# Schematic.net
KiCad netlist of a schematic drawn in EAGLE
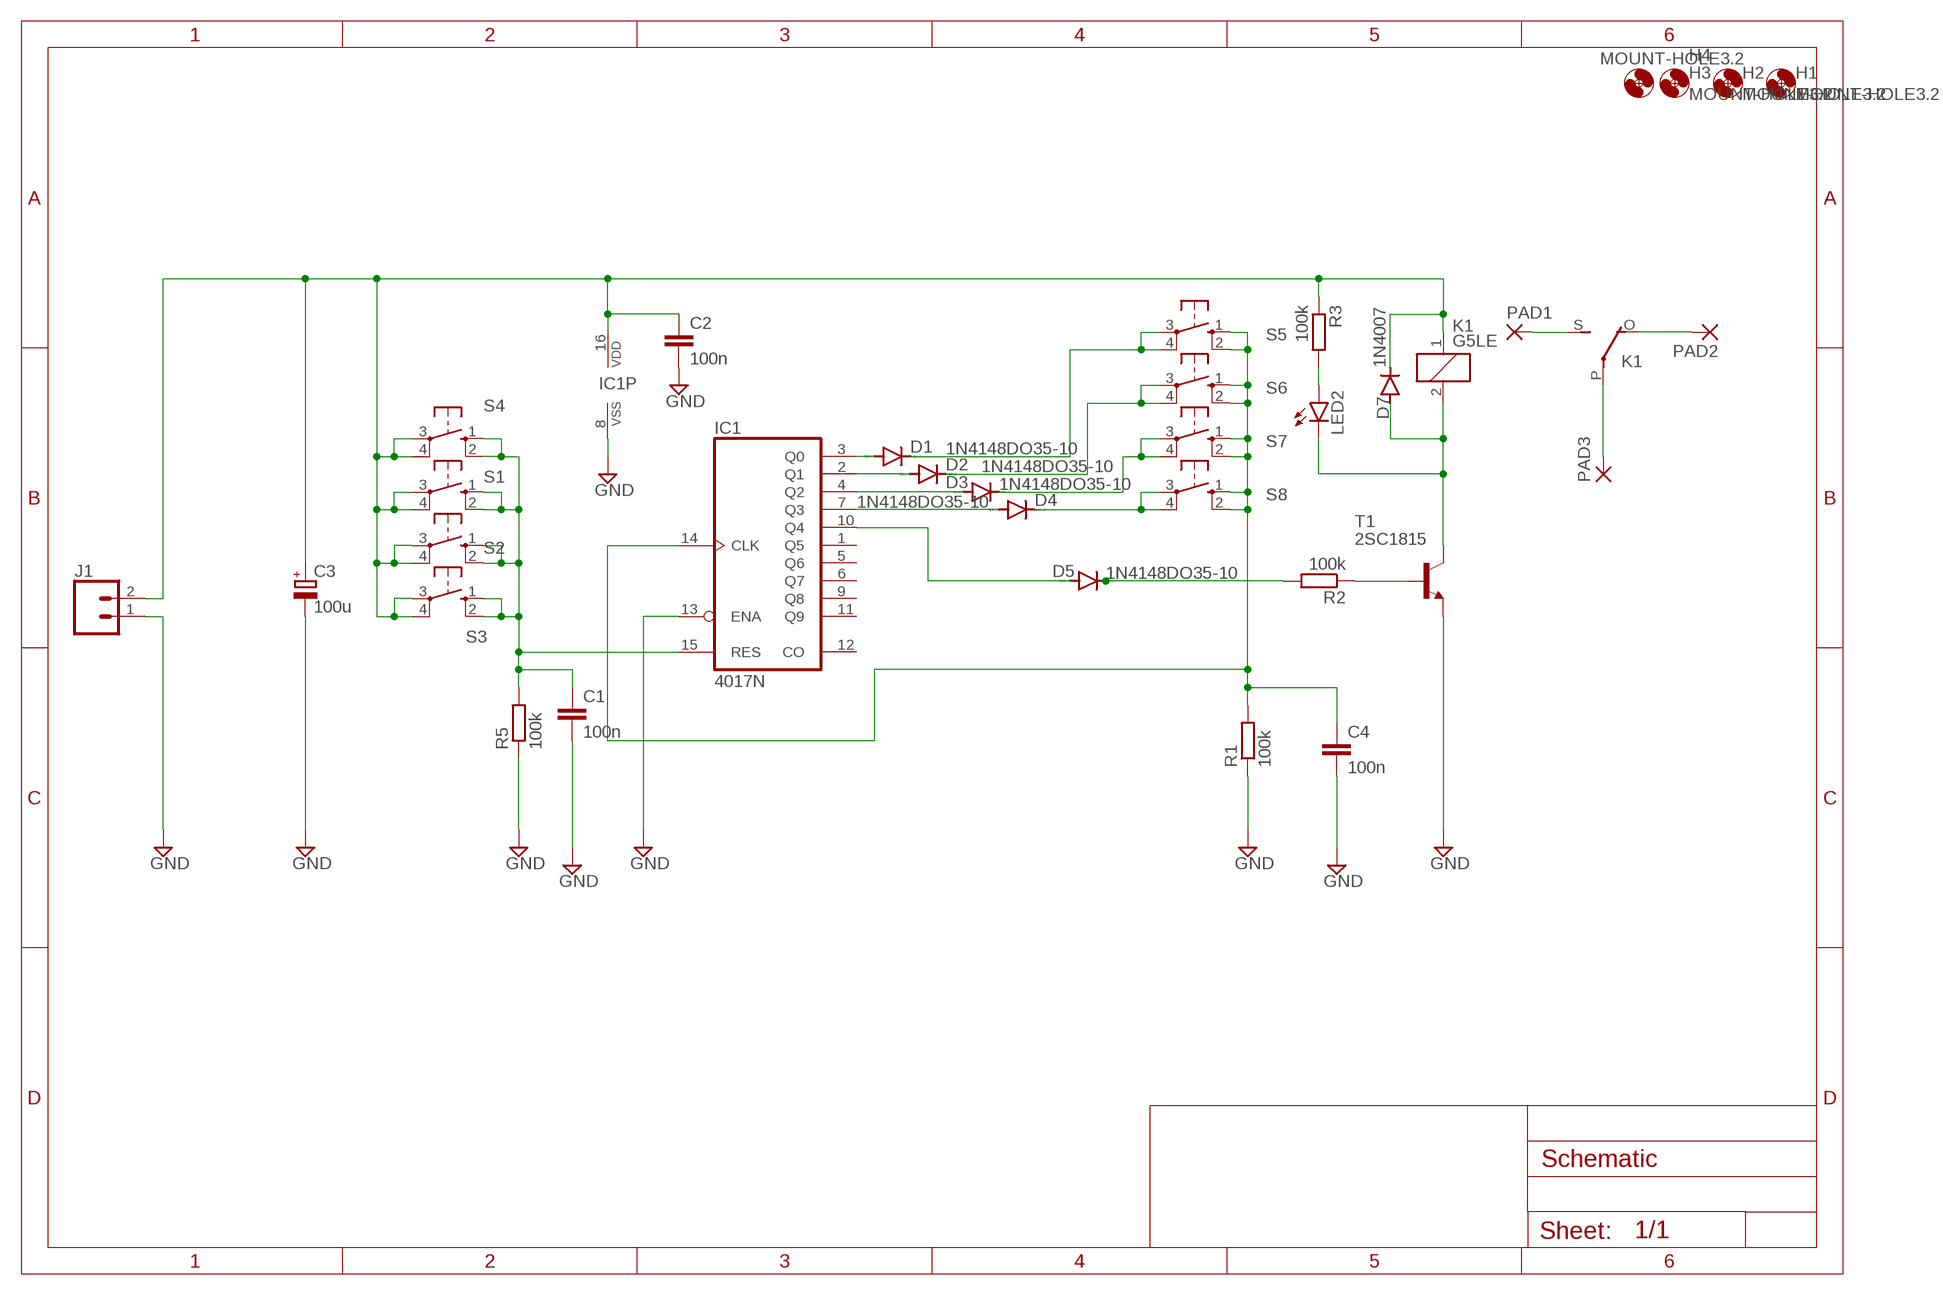
[diagram p0: schematic, sheet 1]

(export (version "E")
  (design (tool "Eeschema 10.0.6"))
  (components
    (comp (ref "C1")
      (value "100n")
      (footprint "eagle-import:C025-060X050")
      (libsource (lib "eagle-import") (part "C-EU025-060X050"))
    )
    (comp (ref "C2")
      (value "100n")
      (footprint "eagle-import:C025-060X050")
      (libsource (lib "eagle-import") (part "C-EU025-060X050"))
    )
    (comp (ref "C3")
      (value "100u")
      (footprint "eagle-import:E2,5-6")
      (libsource (lib "eagle-import") (part "CPOL-EUE2.5-6"))
    )
    (comp (ref "C4")
      (value "100n")
      (footprint "eagle-import:C025-060X050")
      (libsource (lib "eagle-import") (part "C-EU025-060X050"))
    )
    (comp (ref "D1")
      (value "1N4148DO35-10")
      (footprint "eagle-import:DO35-10")
      (libsource (lib "eagle-import") (part "1N4148DO35-10"))
    )
    (comp (ref "D2")
      (value "1N4148DO35-10")
      (footprint "eagle-import:DO35-10")
      (libsource (lib "eagle-import") (part "1N4148DO35-10"))
    )
    (comp (ref "D3")
      (value "1N4148DO35-10")
      (footprint "eagle-import:DO35-10")
      (libsource (lib "eagle-import") (part "1N4148DO35-10"))
    )
    (comp (ref "D4")
      (value "1N4148DO35-10")
      (footprint "eagle-import:DO35-10")
      (libsource (lib "eagle-import") (part "1N4148DO35-10"))
    )
    (comp (ref "D5")
      (value "1N4148DO35-10")
      (footprint "eagle-import:DO35-10")
      (libsource (lib "eagle-import") (part "1N4148DO35-10"))
    )
    (comp (ref "D7")
      (value "1N4007")
      (footprint "eagle-import:DO-41")
      (fields
        (field (name "DIGIKEY_PART_NUMBER") "1N4007MSCT-ND")
        (field (name "MANUFACTURER") "Micro Commercial Co")
        (field (name "CREATED_BY") "PCBLayout.com")
      )
      (libsource (lib "eagle-import") (part "1N4007"))
    )
    (comp (ref "H1")
      (value "MOUNT-HOLE3.2")
      (footprint "eagle-import:3,2")
      (libsource (lib "eagle-import") (part "MOUNT-HOLE3.2"))
    )
    (comp (ref "H2")
      (value "MOUNT-HOLE3.2")
      (footprint "eagle-import:3,2")
      (libsource (lib "eagle-import") (part "MOUNT-HOLE3.2"))
    )
    (comp (ref "H3")
      (value "MOUNT-HOLE3.2")
      (footprint "eagle-import:3,2")
      (libsource (lib "eagle-import") (part "MOUNT-HOLE3.2"))
    )
    (comp (ref "H4")
      (value "MOUNT-HOLE3.2")
      (footprint "eagle-import:3,2")
      (libsource (lib "eagle-import") (part "MOUNT-HOLE3.2"))
    )
    (comp (ref "IC1")
      (value "4017N")
      (footprint "eagle-import:DIL16")
      (libsource (lib "eagle-import") (part "4017N"))
    )
    (comp (ref "J1")
      (value "CONN_023.5MM")
      (footprint "eagle-import:SCREWTERMINAL-3.5MM-2")
      (libsource (lib "eagle-import") (part "CONN_023.5MM"))
    )
    (comp (ref "K1")
      (value "G5LE")
      (footprint "eagle-import:G5LE")
      (libsource (lib "eagle-import") (part "G5LE"))
    )
    (comp (ref "LED2")
      (value "LED5MM")
      (footprint "eagle-import:LED5MM")
      (libsource (lib "eagle-import") (part "LED5MM"))
    )
    (comp (ref "PAD1")
      (value "3,81/1,4")
      (footprint "eagle-import:3,81_1,4")
      (libsource (lib "eagle-import") (part "3,81/1,4"))
    )
    (comp (ref "PAD2")
      (value "3,81/1,4")
      (footprint "eagle-import:3,81_1,4")
      (libsource (lib "eagle-import") (part "3,81/1,4"))
    )
    (comp (ref "PAD3")
      (value "3,81/1,4")
      (footprint "eagle-import:3,81_1,4")
      (libsource (lib "eagle-import") (part "3,81/1,4"))
    )
    (comp (ref "R1")
      (value "100k")
      (footprint "eagle-import:0207_12")
      (libsource (lib "eagle-import") (part "R-EU_0207/12"))
    )
    (comp (ref "R2")
      (value "100k")
      (footprint "eagle-import:0207_12")
      (libsource (lib "eagle-import") (part "R-EU_0207/12"))
    )
    (comp (ref "R3")
      (value "100k")
      (footprint "eagle-import:0207_12")
      (libsource (lib "eagle-import") (part "R-EU_0207/12"))
    )
    (comp (ref "R5")
      (value "100k")
      (footprint "eagle-import:0207_12")
      (libsource (lib "eagle-import") (part "R-EU_0207/12"))
    )
    (comp (ref "S1")
      (value "10-XX")
      (footprint "eagle-import:B3F-10XX")
      (fields (field (name "MPN") "B3F-1000"))
      (libsource (lib "eagle-import") (part "10-XX"))
    )
    (comp (ref "S2")
      (value "10-XX")
      (footprint "eagle-import:B3F-10XX")
      (fields (field (name "MPN") "B3F-1000"))
      (libsource (lib "eagle-import") (part "10-XX"))
    )
    (comp (ref "S3")
      (value "10-XX")
      (footprint "eagle-import:B3F-10XX")
      (fields (field (name "MPN") "B3F-1000"))
      (libsource (lib "eagle-import") (part "10-XX"))
    )
    (comp (ref "S4")
      (value "10-XX")
      (footprint "eagle-import:B3F-10XX")
      (fields (field (name "MPN") "B3F-1000"))
      (libsource (lib "eagle-import") (part "10-XX"))
    )
    (comp (ref "S5")
      (value "10-XX")
      (footprint "eagle-import:B3F-10XX")
      (fields (field (name "MPN") "B3F-1000"))
      (libsource (lib "eagle-import") (part "10-XX"))
    )
    (comp (ref "S6")
      (value "10-XX")
      (footprint "eagle-import:B3F-10XX")
      (fields (field (name "MPN") "B3F-1000"))
      (libsource (lib "eagle-import") (part "10-XX"))
    )
    (comp (ref "S7")
      (value "10-XX")
      (footprint "eagle-import:B3F-10XX")
      (fields (field (name "MPN") "B3F-1000"))
      (libsource (lib "eagle-import") (part "10-XX"))
    )
    (comp (ref "S8")
      (value "10-XX")
      (footprint "eagle-import:B3F-10XX")
      (fields (field (name "MPN") "B3F-1000"))
      (libsource (lib "eagle-import") (part "10-XX"))
    )
    (comp (ref "T1")
      (value "2SC1815")
      (footprint "eagle-import:TO92-ECB")
      (libsource (lib "eagle-import") (part "2SC1815"))
    )
  )
  (nets
    (net (code "1") (name "GND") (class "Default")
      (node (ref "C1") (pin "2") (pinfunction "2_2") (pintype "passive"))
      (node (ref "C2") (pin "2") (pinfunction "2_2") (pintype "passive"))
      (node (ref "C3") (pin "-") (pinfunction "-_-") (pintype "passive"))
      (node (ref "C4") (pin "2") (pinfunction "2_2") (pintype "passive"))
      (node (ref "IC1") (pin "13") (pinfunction "ENA_13") (pintype "input"))
      (node (ref "IC1") (pin "8") (pinfunction "VSS_8") (pintype "power_in"))
      (node (ref "J1") (pin "1") (pinfunction "1_1") (pintype "passive"))
      (node (ref "R1") (pin "1") (pinfunction "1_1") (pintype "passive"))
      (node (ref "R5") (pin "1") (pinfunction "1_1") (pintype "passive"))
      (node (ref "T1") (pin "E") (pinfunction "E_E") (pintype "passive"))
    )
    (net (code "2") (name "Net-(D5-PadC)") (class "Default")
      (node (ref "D5") (pin "C") (pinfunction "C_C") (pintype "passive"))
      (node (ref "R2") (pin "2") (pinfunction "2_2") (pintype "passive"))
    )
    (net (code "3") (name "Net-(IC1A-CLK)") (class "Default")
      (node (ref "C4") (pin "1") (pinfunction "1_1") (pintype "passive"))
      (node (ref "IC1") (pin "14") (pinfunction "CLK_14") (pintype "input"))
      (node (ref "R1") (pin "2") (pinfunction "2_2") (pintype "passive"))
      (node (ref "S5") (pin "1") (pinfunction "S_1") (pintype "passive"))
      (node (ref "S5") (pin "2") (pinfunction "S1_2") (pintype "passive"))
      (node (ref "S6") (pin "1") (pinfunction "S_1") (pintype "passive"))
      (node (ref "S6") (pin "2") (pinfunction "S1_2") (pintype "passive"))
      (node (ref "S7") (pin "1") (pinfunction "S_1") (pintype "passive"))
      (node (ref "S7") (pin "2") (pinfunction "S1_2") (pintype "passive"))
      (node (ref "S8") (pin "1") (pinfunction "S_1") (pintype "passive"))
      (node (ref "S8") (pin "2") (pinfunction "S1_2") (pintype "passive"))
    )
    (net (code "4") (name "Net-(IC1A-Q0)") (class "Default")
      (node (ref "D1") (pin "A") (pinfunction "A_A") (pintype "passive"))
      (node (ref "IC1") (pin "3") (pinfunction "Q0_3") (pintype "output"))
    )
    (net (code "5") (name "Net-(IC1A-Q1)") (class "Default")
      (node (ref "D2") (pin "A") (pinfunction "A_A") (pintype "passive"))
      (node (ref "IC1") (pin "2") (pinfunction "Q1_2") (pintype "output"))
    )
    (net (code "6") (name "Net-(IC1A-Q2)") (class "Default")
      (node (ref "D3") (pin "A") (pinfunction "A_A") (pintype "passive"))
      (node (ref "IC1") (pin "4") (pinfunction "Q2_4") (pintype "output"))
    )
    (net (code "7") (name "Net-(IC1A-Q3)") (class "Default")
      (node (ref "D4") (pin "A") (pinfunction "A_A") (pintype "passive"))
      (node (ref "IC1") (pin "7") (pinfunction "Q3_7") (pintype "output"))
    )
    (net (code "8") (name "Net-(IC1A-Q4)") (class "Default")
      (node (ref "D5") (pin "A") (pinfunction "A_A") (pintype "passive"))
      (node (ref "IC1") (pin "10") (pinfunction "Q4_10") (pintype "output"))
    )
    (net (code "9") (name "Net-(IC1A-RES)") (class "Default")
      (node (ref "C1") (pin "1") (pinfunction "1_1") (pintype "passive"))
      (node (ref "IC1") (pin "15") (pinfunction "RES_15") (pintype "input"))
      (node (ref "R5") (pin "2") (pinfunction "2_2") (pintype "passive"))
      (node (ref "S1") (pin "1") (pinfunction "S_1") (pintype "passive"))
      (node (ref "S1") (pin "2") (pinfunction "S1_2") (pintype "passive"))
      (node (ref "S2") (pin "1") (pinfunction "S_1") (pintype "passive"))
      (node (ref "S2") (pin "2") (pinfunction "S1_2") (pintype "passive"))
      (node (ref "S3") (pin "1") (pinfunction "S_1") (pintype "passive"))
      (node (ref "S3") (pin "2") (pinfunction "S1_2") (pintype "passive"))
      (node (ref "S4") (pin "1") (pinfunction "S_1") (pintype "passive"))
      (node (ref "S4") (pin "2") (pinfunction "S1_2") (pintype "passive"))
    )
    (net (code "10") (name "Net-(IC1B-VDD)") (class "Default")
      (node (ref "C2") (pin "1") (pinfunction "1_1") (pintype "passive"))
      (node (ref "C3") (pin "+") (pinfunction "+_+") (pintype "passive"))
      (node (ref "D7") (pin "C") (pinfunction "C_C") (pintype "passive"))
      (node (ref "IC1") (pin "16") (pinfunction "VDD_16") (pintype "power_in"))
      (node (ref "J1") (pin "2") (pinfunction "2_2") (pintype "passive"))
      (node (ref "K1") (pin "1") (pinfunction "1_1") (pintype "passive"))
      (node (ref "R3") (pin "1") (pinfunction "1_1") (pintype "passive"))
      (node (ref "S1") (pin "3") (pinfunction "P_3") (pintype "passive"))
      (node (ref "S1") (pin "4") (pinfunction "P1_4") (pintype "passive"))
      (node (ref "S2") (pin "3") (pinfunction "P_3") (pintype "passive"))
      (node (ref "S2") (pin "4") (pinfunction "P1_4") (pintype "passive"))
      (node (ref "S3") (pin "3") (pinfunction "P_3") (pintype "passive"))
      (node (ref "S3") (pin "4") (pinfunction "P1_4") (pintype "passive"))
      (node (ref "S4") (pin "3") (pinfunction "P_3") (pintype "passive"))
      (node (ref "S4") (pin "4") (pinfunction "P1_4") (pintype "passive"))
    )
    (net (code "11") (name "Net-(LED2-C)") (class "Default")
      (node (ref "D7") (pin "A") (pinfunction "A_A") (pintype "passive"))
      (node (ref "K1") (pin "2") (pinfunction "2_2") (pintype "passive"))
      (node (ref "LED2") (pin "K") (pinfunction "C_K") (pintype "passive"))
      (node (ref "T1") (pin "C") (pinfunction "C_C") (pintype "passive"))
    )
    (net (code "12") (name "Net-(LED2-PadA)") (class "Default")
      (node (ref "LED2") (pin "A") (pinfunction "A_A") (pintype "passive"))
      (node (ref "R3") (pin "2") (pinfunction "2_2") (pintype "passive"))
    )
    (net (code "13") (name "Net-(PAD1-P)") (class "Default")
      (node (ref "K1") (pin "S") (pinfunction "S_S") (pintype "passive"))
      (node (ref "PAD1") (pin "1") (pinfunction "P_1") (pintype "passive"))
    )
    (net (code "14") (name "Net-(PAD2-P)") (class "Default")
      (node (ref "K1") (pin "O") (pinfunction "O_O") (pintype "passive"))
      (node (ref "PAD2") (pin "1") (pinfunction "P_1") (pintype "passive"))
    )
    (net (code "15") (name "Net-(PAD3-P)") (class "Default")
      (node (ref "K1") (pin "P") (pinfunction "P_P") (pintype "passive"))
      (node (ref "PAD3") (pin "1") (pinfunction "P_1") (pintype "passive"))
    )
    (net (code "16") (name "Net-(R2-Pad1)") (class "Default")
      (node (ref "R2") (pin "1") (pinfunction "1_1") (pintype "passive"))
      (node (ref "T1") (pin "B") (pinfunction "B_B") (pintype "passive"))
    )
    (net (code "17") (name "Net-(S5-P)") (class "Default")
      (node (ref "D1") (pin "C") (pinfunction "C_C") (pintype "passive"))
      (node (ref "S5") (pin "3") (pinfunction "P_3") (pintype "passive"))
      (node (ref "S5") (pin "4") (pinfunction "P1_4") (pintype "passive"))
    )
    (net (code "18") (name "Net-(S6-P)") (class "Default")
      (node (ref "D2") (pin "C") (pinfunction "C_C") (pintype "passive"))
      (node (ref "S6") (pin "3") (pinfunction "P_3") (pintype "passive"))
      (node (ref "S6") (pin "4") (pinfunction "P1_4") (pintype "passive"))
    )
    (net (code "19") (name "Net-(S7-P)") (class "Default")
      (node (ref "D3") (pin "C") (pinfunction "C_C") (pintype "passive"))
      (node (ref "S7") (pin "3") (pinfunction "P_3") (pintype "passive"))
      (node (ref "S7") (pin "4") (pinfunction "P1_4") (pintype "passive"))
    )
    (net (code "20") (name "Net-(S8-P)") (class "Default")
      (node (ref "D4") (pin "C") (pinfunction "C_C") (pintype "passive"))
      (node (ref "S8") (pin "3") (pinfunction "P_3") (pintype "passive"))
      (node (ref "S8") (pin "4") (pinfunction "P1_4") (pintype "passive"))
    )
    (net (code "21") (name "unconnected-(IC1A-CO-Pad12)") (class "Default")
      (node (ref "IC1") (pin "12") (pinfunction "CO_12") (pintype "output"))
    )
    (net (code "22") (name "unconnected-(IC1A-Q5-Pad1)") (class "Default")
      (node (ref "IC1") (pin "1") (pinfunction "Q5_1") (pintype "output"))
    )
    (net (code "23") (name "unconnected-(IC1A-Q6-Pad5)") (class "Default")
      (node (ref "IC1") (pin "5") (pinfunction "Q6_5") (pintype "output"))
    )
    (net (code "24") (name "unconnected-(IC1A-Q7-Pad6)") (class "Default")
      (node (ref "IC1") (pin "6") (pinfunction "Q7_6") (pintype "output"))
    )
    (net (code "25") (name "unconnected-(IC1A-Q8-Pad9)") (class "Default")
      (node (ref "IC1") (pin "9") (pinfunction "Q8_9") (pintype "output"))
    )
    (net (code "26") (name "unconnected-(IC1A-Q9-Pad11)") (class "Default")
      (node (ref "IC1") (pin "11") (pinfunction "Q9_11") (pintype "output"))
    )
  )
)
